# OSB_GRF.net
KiCad netlist of a schematic drawn in EAGLE
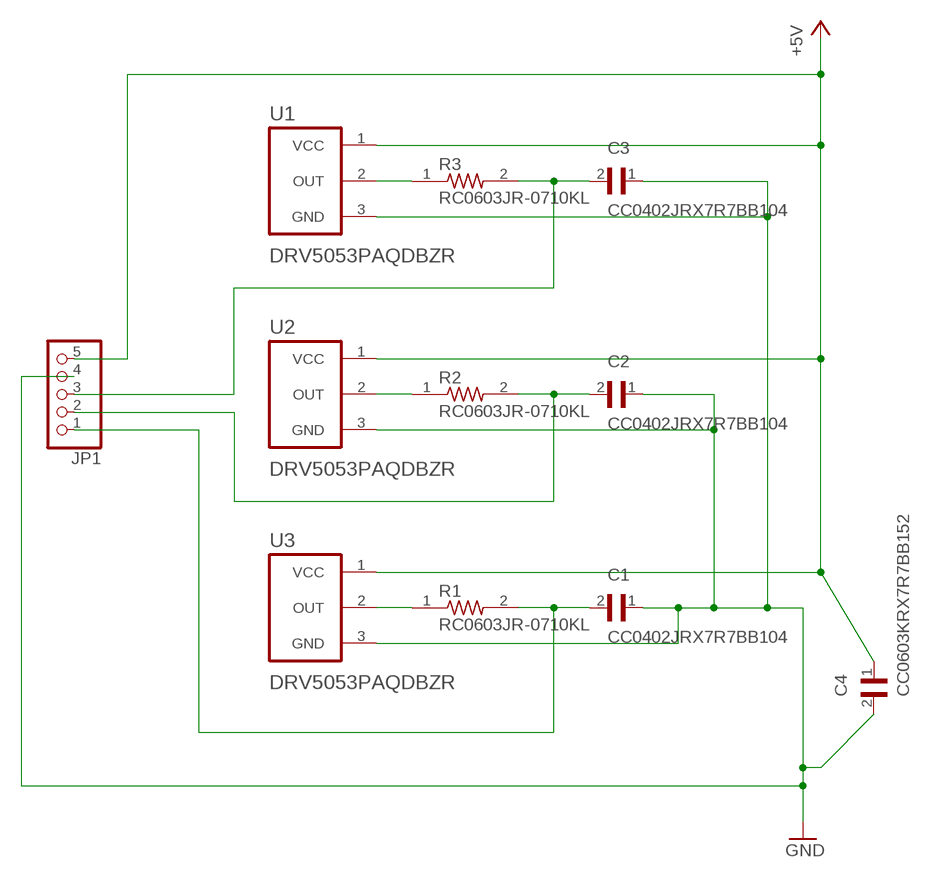
[diagram p0: schematic, sheet 1]

(export (version "E")
  (design (tool "Eeschema 10.0.6"))
  (components
    (comp (ref "C1")
      (value "CC0402JRX7R7BB104")
      (footprint "eagle-import:CAPC1005X55N")
      (fields (field (name "DIGI-KEY_PART_NUMBER") "311-1676-1-ND") (field (name "MF") "Yageo"))
      (libsource (lib "eagle-import") (part "CC0402JRX7R7BB104"))
    )
    (comp (ref "C2")
      (value "CC0402JRX7R7BB104")
      (footprint "eagle-import:CAPC1005X55N")
      (fields (field (name "DIGI-KEY_PART_NUMBER") "311-1676-1-ND") (field (name "MF") "Yageo"))
      (libsource (lib "eagle-import") (part "CC0402JRX7R7BB104"))
    )
    (comp (ref "C3")
      (value "CC0402JRX7R7BB104")
      (footprint "eagle-import:CAPC1005X55N")
      (fields (field (name "DIGI-KEY_PART_NUMBER") "311-1676-1-ND") (field (name "MF") "Yageo"))
      (libsource (lib "eagle-import") (part "CC0402JRX7R7BB104"))
    )
    (comp (ref "C4")
      (value "CC0603KRX7R7BB152")
      (footprint "eagle-import:CAPC1608X90")
      (fields (field (name "DIGI-KEY_PART_NUMBER") "311-4064-1-ND") (field (name "MF") "Yageo"))
      (libsource (lib "eagle-import") (part "CC0603KRX7R7BB152"))
    )
    (comp (ref "JP1")
      (value "PINHD-1X55X2MM")
      (footprint "eagle-import:1_05X2MM")
      (libsource (lib "eagle-import") (part "PINHD-1X55X2MM"))
    )
    (comp (ref "R1")
      (value "RC0603JR-0710KL")
      (footprint "eagle-import:RESC1607X60N")
      (fields (field (name "DIGI-KEY_PART_NUMBER") "311-10KGRCT-ND") (field (name "MF") "Yageo"))
      (libsource (lib "eagle-import") (part "RC0603JR-0710KL"))
    )
    (comp (ref "R2")
      (value "RC0603JR-0710KL")
      (footprint "eagle-import:RESC1607X60N")
      (fields (field (name "DIGI-KEY_PART_NUMBER") "311-10KGRCT-ND") (field (name "MF") "Yageo"))
      (libsource (lib "eagle-import") (part "RC0603JR-0710KL"))
    )
    (comp (ref "R3")
      (value "RC0603JR-0710KL")
      (footprint "eagle-import:RESC1607X60N")
      (fields (field (name "DIGI-KEY_PART_NUMBER") "311-10KGRCT-ND") (field (name "MF") "Yageo"))
      (libsource (lib "eagle-import") (part "RC0603JR-0710KL"))
    )
    (comp (ref "U1")
      (value "DRV5053PAQDBZR")
      (footprint "eagle-import:SOT95P237X112-3N")
      (fields (field (name "DIGI-KEY_PART_NUMBER") "296-38458-1-ND") (field (name "MF") "Texas Instruments"))
      (libsource (lib "eagle-import") (part "DRV5053PAQDBZR"))
    )
    (comp (ref "U2")
      (value "DRV5053PAQDBZR")
      (footprint "eagle-import:SOT95P237X112-3N")
      (fields (field (name "DIGI-KEY_PART_NUMBER") "296-38458-1-ND") (field (name "MF") "Texas Instruments"))
      (libsource (lib "eagle-import") (part "DRV5053PAQDBZR"))
    )
    (comp (ref "U3")
      (value "DRV5053PAQDBZR")
      (footprint "eagle-import:SOT95P237X112-3N")
      (fields (field (name "DIGI-KEY_PART_NUMBER") "296-38458-1-ND") (field (name "MF") "Texas Instruments"))
      (libsource (lib "eagle-import") (part "DRV5053PAQDBZR"))
    )
  )
  (nets
    (net (code "1") (name "+5V") (class "Default")
      (node (ref "C4") (pin "1") (pinfunction "1_1") (pintype "passive"))
      (node (ref "JP1") (pin "5") (pinfunction "5_5") (pintype "passive"))
      (node (ref "U1") (pin "1") (pinfunction "VCC_1") (pintype "power_in"))
      (node (ref "U2") (pin "1") (pinfunction "VCC_1") (pintype "power_in"))
      (node (ref "U3") (pin "1") (pinfunction "VCC_1") (pintype "power_in"))
    )
    (net (code "2") (name "GND") (class "Default")
      (node (ref "C1") (pin "1") (pinfunction "1_1") (pintype "passive"))
      (node (ref "C2") (pin "1") (pinfunction "1_1") (pintype "passive"))
      (node (ref "C3") (pin "1") (pinfunction "1_1") (pintype "passive"))
      (node (ref "C4") (pin "2") (pinfunction "2_2") (pintype "passive"))
      (node (ref "JP1") (pin "4") (pinfunction "4_4") (pintype "passive"))
      (node (ref "U1") (pin "3") (pinfunction "GND_3") (pintype "power_in"))
      (node (ref "U2") (pin "3") (pinfunction "GND_3") (pintype "power_in"))
      (node (ref "U3") (pin "3") (pinfunction "GND_3") (pintype "power_in"))
    )
    (net (code "3") (name "Net-(C1-Pad2)") (class "Default")
      (node (ref "C1") (pin "2") (pinfunction "2_2") (pintype "passive"))
      (node (ref "JP1") (pin "1") (pinfunction "1_1") (pintype "passive"))
      (node (ref "R1") (pin "2") (pinfunction "2_2") (pintype "passive"))
    )
    (net (code "4") (name "Net-(C2-Pad2)") (class "Default")
      (node (ref "C2") (pin "2") (pinfunction "2_2") (pintype "passive"))
      (node (ref "JP1") (pin "2") (pinfunction "2_2") (pintype "passive"))
      (node (ref "R2") (pin "2") (pinfunction "2_2") (pintype "passive"))
    )
    (net (code "5") (name "Net-(C3-Pad2)") (class "Default")
      (node (ref "C3") (pin "2") (pinfunction "2_2") (pintype "passive"))
      (node (ref "JP1") (pin "3") (pinfunction "3_3") (pintype "passive"))
      (node (ref "R3") (pin "2") (pinfunction "2_2") (pintype "passive"))
    )
    (net (code "6") (name "Net-(U1-OUT)") (class "Default")
      (node (ref "R3") (pin "1") (pinfunction "1_1") (pintype "passive"))
      (node (ref "U1") (pin "2") (pinfunction "OUT_2") (pintype "output"))
    )
    (net (code "7") (name "Net-(U2-OUT)") (class "Default")
      (node (ref "R2") (pin "1") (pinfunction "1_1") (pintype "passive"))
      (node (ref "U2") (pin "2") (pinfunction "OUT_2") (pintype "output"))
    )
    (net (code "8") (name "Net-(U3-OUT)") (class "Default")
      (node (ref "R1") (pin "1") (pinfunction "1_1") (pintype "passive"))
      (node (ref "U3") (pin "2") (pinfunction "OUT_2") (pintype "output"))
    )
  )
)
